# CH32V007K8U6-R0.net
KiCad netlist of a schematic drawn in Altium Designer
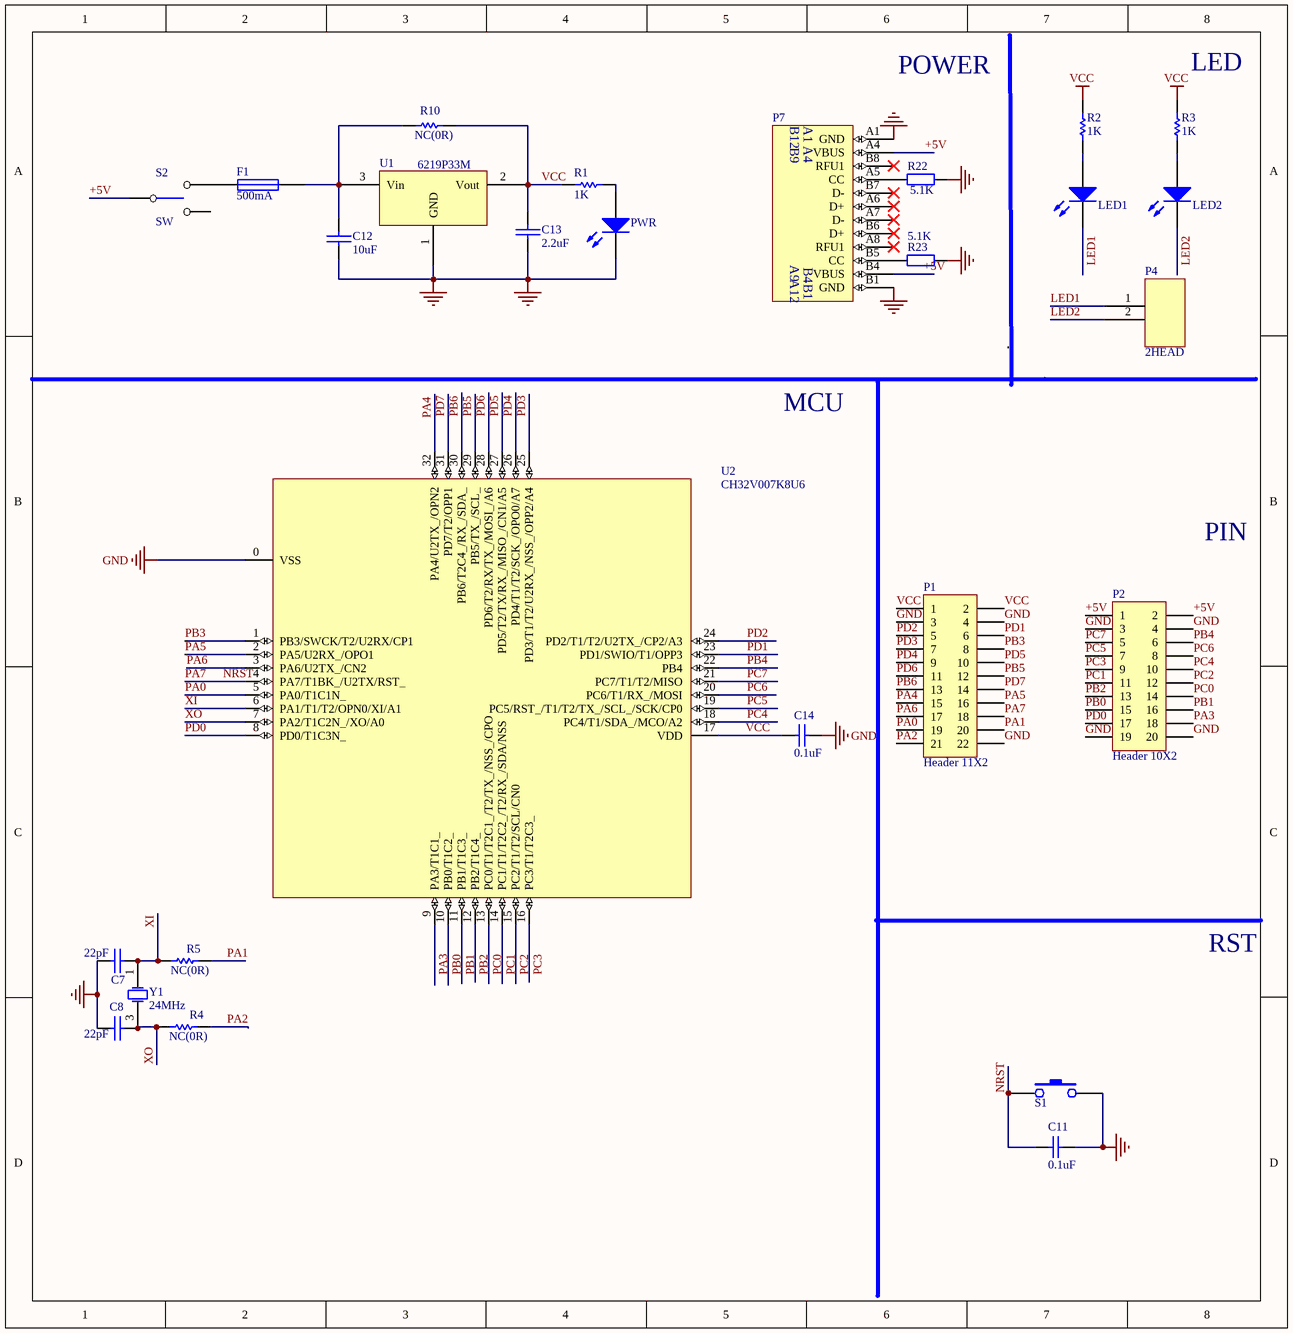
[diagram p0: CH32V007K8U6-R0.SchDoc]

(export (version "E")
  (design (tool "Eeschema 10.0.6"))
  (components
    (comp (ref "C7")
      (value "22pF")
      (footprint "0402_C")
      (description "Capacitor")
      (libsource (lib "*") (part "CAP"))
    )
    (comp (ref "C8")
      (value "22pF")
      (footprint "0402_C")
      (description "Capacitor")
      (libsource (lib "*") (part "CAP"))
    )
    (comp (ref "C11")
      (value "0.1uF")
      (footprint "0402_C")
      (description "Capacitor")
      (fields (field (name "PUBLISHER") "Altium Limited"))
      (libsource (lib "*") (part "Cap"))
    )
    (comp (ref "C12")
      (value "10uF")
      (footprint "0603_C")
      (description "Capacitor")
      (libsource (lib "wch_sch_others") (part "CAP"))
    )
    (comp (ref "C13")
      (value "2.2uF")
      (footprint "0402_C")
      (description "Capacitor")
      (libsource (lib "wch_sch_others") (part "CAP"))
    )
    (comp (ref "C14")
      (value "0.1uF")
      (footprint "0402_C")
      (description "Capacitor")
      (fields (field (name "PUBLISHER") "Altium Limited"))
      (libsource (lib "*") (part "Cap"))
    )
    (comp (ref "F1")
      (value "500mA")
      (footprint "0603")
      (description "Fuse")
      (libsource (lib "*") (part "FUSE1"))
    )
    (comp (ref "LED1")
      (value "LED1   blue")
      (footprint "0603+")
      (description "Typical INFRARED GaAs LED")
      (fields (field (name "PUBLISHER") "Altium Limited"))
      (libsource (lib "*") (part "LED0"))
    )
    (comp (ref "LED2")
      (value "LED2  blue")
      (footprint "0603+")
      (description "Typical INFRARED GaAs LED")
      (fields (field (name "PUBLISHER") "Altium Limited"))
      (libsource (lib "*") (part "LED0"))
    )
    (comp (ref "P1")
      (value "Header 11X2")
      (footprint "IDC22-2.54mm")
      (description "Header, 11-Pin, Dual row")
      (fields (field (name "PUBLISHER") "Altium Limited"))
      (libsource (lib "Miscellaneous Connectors") (part "Header 11X2"))
    )
    (comp (ref "P2")
      (value "Header 10X2")
      (footprint "IDC20-2.54mm")
      (description "Header, 10-Pin, Dual row")
      (fields (field (name "PUBLISHER") "Altium Limited"))
      (libsource (lib "Miscellaneous Connectors") (part "Header 10X2"))
    )
    (comp (ref "P4") (value "2HEAD") (footprint "SIP2-2.54mm") (libsource (lib "*") (part "2HEAD")))
    (comp (ref "P7")
      (value "TYPE-C")
      (footprint "TYPE-C-Receptacle-2.0")
      (libsource (lib "*") (part "TYPE-C1"))
    )
    (comp (ref "PWR")
      (value "POWER  red")
      (footprint "0603+")
      (description "Typical INFRARED GaAs LED")
      (fields (field (name "PUBLISHER") "Altium Limited"))
      (libsource (lib "") (part "LED0_1"))
    )
    (comp (ref "R1")
      (value "1K")
      (footprint "0402")
      (description "Semiconductor Resistor")
      (fields (field (name "PUBLISHER") "Altium Limited"))
      (libsource (lib "*") (part "Res Semi"))
    )
    (comp (ref "R2")
      (value "1K")
      (footprint "0402")
      (description "Semiconductor Resistor")
      (fields (field (name "PUBLISHER") "Altium Limited"))
      (libsource (lib "*") (part "Res Semi"))
    )
    (comp (ref "R3")
      (value "1K")
      (footprint "0402")
      (description "Semiconductor Resistor")
      (fields (field (name "PUBLISHER") "Altium Limited"))
      (libsource (lib "*") (part "Res Semi"))
    )
    (comp (ref "R4")
      (value "NC(0R)")
      (footprint "0402")
      (description "Semiconductor Resistor")
      (fields (field (name "Comment") "0R") (field (name "PUBLISHER") "Altium Limited"))
      (libsource (lib "*") (part "Res Semi"))
    )
    (comp (ref "R5")
      (value "NC(0R)")
      (footprint "0402")
      (description "Semiconductor Resistor")
      (fields (field (name "Comment") "0R") (field (name "PUBLISHER") "Altium Limited"))
      (libsource (lib "*") (part "Res Semi"))
    )
    (comp (ref "R10")
      (value "NC(0R)")
      (footprint "0402")
      (description "Semiconductor Resistor")
      (fields (field (name "Comment") "0R") (field (name "PUBLISHER") "Altium Limited"))
      (libsource (lib "*") (part "Res Semi"))
    )
    (comp (ref "R22")
      (value "5.1K")
      (footprint "0402")
      (description "Resistor")
      (libsource (lib "Miscellaneous Devices") (part "Res2"))
    )
    (comp (ref "R23")
      (value "5.1K")
      (footprint "0402")
      (description "Resistor")
      (libsource (lib "Miscellaneous Devices") (part "Res2"))
    )
    (comp (ref "S1") (value "NRST") (footprint "SMD_6.1x3.65x2.5mm-KEY") (libsource (lib "*") (part "KEY")))
    (comp (ref "S2") (value "SW") (footprint "SW1") (libsource (lib "*") (part "SW")))
    (comp (ref "U1")
      (value "6219P33M")
      (footprint "SOT-23")
      (libsource (lib "wch_sch_others") (part "6219P33M"))
    )
    (comp (ref "U2")
      (value "CH32V007K8U6")
      (footprint "QFN32_4X4")
      (description "RISC-V MCU, ADC/OPA/CMP/2*UART/I2C/SPI")
      (libsource (lib "DHXXXSCH") (part "CH32V007K8U6"))
    )
    (comp (ref "Y1")
      (value "24MHz")
      (footprint "XT3225")
      (description "Crystal Oscillator")
      (fields (field (name "PUBLISHER") "Altium Limited"))
      (libsource (lib "*") (part "XTAL"))
    )
  )
  (nets
    (net (code "1") (name "/+5V") (class "Default")
      (node (ref "P2") (pin "1") (pinfunction "1_1") (pintype "passive"))
      (node (ref "P2") (pin "2") (pinfunction "2_2") (pintype "passive"))
      (node (ref "P7") (pin "A4") (pinfunction "VBUS_A4") (pintype "bidirectional"))
      (node (ref "P7") (pin "B4") (pinfunction "VBUS_B4") (pintype "bidirectional"))
      (node (ref "S2") (pin "1") (pinfunction "1_1") (pintype "passive"))
    )
    (net (code "2") (name "/LED1") (class "Default")
      (node (ref "LED1") (pin "2") (pinfunction "K_2") (pintype "passive"))
      (node (ref "P4") (pin "1") (pintype "passive"))
    )
    (net (code "3") (name "/LED2") (class "Default")
      (node (ref "LED2") (pin "2") (pinfunction "K_2") (pintype "passive"))
      (node (ref "P4") (pin "2") (pintype "passive"))
    )
    (net (code "4") (name "/NRST") (class "Default")
      (node (ref "C11") (pin "2") (pinfunction "2_2") (pintype "passive"))
      (node (ref "P1") (pin "18") (pinfunction "18_18") (pintype "passive"))
      (node (ref "S1") (pin "1") (pinfunction "1_1") (pintype "passive"))
      (node (ref "U2") (pin "4") (pinfunction "PA7/T1BK_/U2TX/RST__4") (pintype "bidirectional"))
    )
    (net (code "5") (name "/PA0") (class "Default")
      (node (ref "P1") (pin "19") (pinfunction "19_19") (pintype "passive"))
      (node (ref "U2") (pin "5") (pinfunction "PA0/T1C1N__5") (pintype "bidirectional"))
    )
    (net (code "6") (name "/PA1") (class "Default")
      (node (ref "P1") (pin "20") (pinfunction "20_20") (pintype "passive"))
      (node (ref "R5") (pin "2") (pinfunction "2_2") (pintype "passive"))
    )
    (net (code "7") (name "/PA2") (class "Default")
      (node (ref "P1") (pin "21") (pinfunction "21_21") (pintype "passive"))
      (node (ref "R4") (pin "2") (pinfunction "2_2") (pintype "passive"))
    )
    (net (code "8") (name "/PA3") (class "Default")
      (node (ref "P2") (pin "18") (pinfunction "18_18") (pintype "passive"))
      (node (ref "U2") (pin "9") (pinfunction "PA3/T1C1__9") (pintype "bidirectional"))
    )
    (net (code "9") (name "/PA4") (class "Default")
      (node (ref "P1") (pin "15") (pinfunction "15_15") (pintype "passive"))
      (node (ref "U2") (pin "32") (pinfunction "PA4/U2TX_/OPN2_32") (pintype "bidirectional"))
    )
    (net (code "10") (name "/PA5") (class "Default")
      (node (ref "P1") (pin "16") (pinfunction "16_16") (pintype "passive"))
      (node (ref "U2") (pin "2") (pinfunction "PA5/U2RX_/OPO1_2") (pintype "bidirectional"))
    )
    (net (code "11") (name "/PA6") (class "Default")
      (node (ref "P1") (pin "17") (pinfunction "17_17") (pintype "passive"))
      (node (ref "U2") (pin "3") (pinfunction "PA6/U2TX_/CN2_3") (pintype "bidirectional"))
    )
    (net (code "12") (name "/PB0") (class "Default")
      (node (ref "P2") (pin "15") (pinfunction "15_15") (pintype "passive"))
      (node (ref "U2") (pin "10") (pinfunction "PB0/T1C2__10") (pintype "bidirectional"))
    )
    (net (code "13") (name "/PB1") (class "Default")
      (node (ref "P2") (pin "16") (pinfunction "16_16") (pintype "passive"))
      (node (ref "U2") (pin "11") (pinfunction "PB1/T1C3__11") (pintype "bidirectional"))
    )
    (net (code "14") (name "/PB2") (class "Default")
      (node (ref "P2") (pin "13") (pinfunction "13_13") (pintype "passive"))
      (node (ref "U2") (pin "12") (pinfunction "PB2/T1C4__12") (pintype "bidirectional"))
    )
    (net (code "15") (name "/PB3") (class "Default")
      (node (ref "P1") (pin "8") (pinfunction "8_8") (pintype "passive"))
      (node (ref "U2") (pin "1") (pinfunction "PB3/SWCK/T2/U2RX/CP1_1") (pintype "bidirectional"))
    )
    (net (code "16") (name "/PB4") (class "Default")
      (node (ref "P2") (pin "6") (pinfunction "6_6") (pintype "passive"))
      (node (ref "U2") (pin "22") (pinfunction "PB4_22") (pintype "bidirectional"))
    )
    (net (code "17") (name "/PB5") (class "Default")
      (node (ref "P1") (pin "12") (pinfunction "12_12") (pintype "passive"))
      (node (ref "U2") (pin "29") (pinfunction "PB5/TX_/SCL__29") (pintype "bidirectional"))
    )
    (net (code "18") (name "/PB6") (class "Default")
      (node (ref "P1") (pin "13") (pinfunction "13_13") (pintype "passive"))
      (node (ref "U2") (pin "30") (pinfunction "PB6/T2C4_/RX_/SDA__30") (pintype "bidirectional"))
    )
    (net (code "19") (name "/PC0") (class "Default")
      (node (ref "P2") (pin "14") (pinfunction "14_14") (pintype "passive"))
      (node (ref "U2") (pin "13") (pinfunction "PC0/T1/T2C1_/T2/TX_/NSS_/CPO_13") (pintype "bidirectional"))
    )
    (net (code "20") (name "/PC1") (class "Default")
      (node (ref "P2") (pin "11") (pinfunction "11_11") (pintype "passive"))
      (node (ref "U2") (pin "14") (pinfunction "PC1/T1/T2C2_/T2/RX_/SDA/NSS_14") (pintype "bidirectional"))
    )
    (net (code "21") (name "/PC2") (class "Default")
      (node (ref "P2") (pin "12") (pinfunction "12_12") (pintype "passive"))
      (node (ref "U2") (pin "15") (pinfunction "PC2/T1/T2/SCL/CN0_15") (pintype "bidirectional"))
    )
    (net (code "22") (name "/PC3") (class "Default")
      (node (ref "P2") (pin "9") (pinfunction "9_9") (pintype "passive"))
      (node (ref "U2") (pin "16") (pinfunction "PC3/T1/T2C3__16") (pintype "bidirectional"))
    )
    (net (code "23") (name "/PC4") (class "Default")
      (node (ref "P2") (pin "10") (pinfunction "10_10") (pintype "passive"))
      (node (ref "U2") (pin "18") (pinfunction "PC4/T1/SDA_/MCO/A2_18") (pintype "bidirectional"))
    )
    (net (code "24") (name "/PC5") (class "Default")
      (node (ref "P2") (pin "7") (pinfunction "7_7") (pintype "passive"))
      (node (ref "U2") (pin "19") (pinfunction "PC5/RST_/T1/T2/TX_/SCL_/SCK/CP0_19") (pintype "bidirectional"))
    )
    (net (code "25") (name "/PC6") (class "Default")
      (node (ref "P2") (pin "8") (pinfunction "8_8") (pintype "passive"))
      (node (ref "U2") (pin "20") (pinfunction "PC6/T1/RX_/MOSI_20") (pintype "bidirectional"))
    )
    (net (code "26") (name "/PC7") (class "Default")
      (node (ref "P2") (pin "5") (pinfunction "5_5") (pintype "passive"))
      (node (ref "U2") (pin "21") (pinfunction "PC7/T1/T2/MISO_21") (pintype "bidirectional"))
    )
    (net (code "27") (name "/PD0") (class "Default")
      (node (ref "P2") (pin "17") (pinfunction "17_17") (pintype "passive"))
      (node (ref "U2") (pin "8") (pinfunction "PD0/T1C3N__8") (pintype "bidirectional"))
    )
    (net (code "28") (name "/PD1") (class "Default")
      (node (ref "P1") (pin "6") (pinfunction "6_6") (pintype "passive"))
      (node (ref "U2") (pin "23") (pinfunction "PD1/SWIO/T1/OPP3_23") (pintype "bidirectional"))
    )
    (net (code "29") (name "/PD2") (class "Default")
      (node (ref "P1") (pin "5") (pinfunction "5_5") (pintype "passive"))
      (node (ref "U2") (pin "24") (pinfunction "PD2/T1/T2/U2TX_/CP2/A3_24") (pintype "bidirectional"))
    )
    (net (code "30") (name "/PD3") (class "Default")
      (node (ref "P1") (pin "7") (pinfunction "7_7") (pintype "passive"))
      (node (ref "U2") (pin "25") (pinfunction "PD3/T1/T2/U2RX_/NSS_/OPP2/A4_25") (pintype "bidirectional"))
    )
    (net (code "31") (name "/PD4") (class "Default")
      (node (ref "P1") (pin "9") (pinfunction "9_9") (pintype "passive"))
      (node (ref "U2") (pin "26") (pinfunction "PD4/T1/T2/SCK_/OPO0/A7_26") (pintype "bidirectional"))
    )
    (net (code "32") (name "/PD5") (class "Default")
      (node (ref "P1") (pin "10") (pinfunction "10_10") (pintype "passive"))
      (node (ref "U2") (pin "27") (pinfunction "PD5/T2/TX/RX_/MISO_/CN1/A5_27") (pintype "bidirectional"))
    )
    (net (code "33") (name "/PD6") (class "Default")
      (node (ref "P1") (pin "11") (pinfunction "11_11") (pintype "passive"))
      (node (ref "U2") (pin "28") (pinfunction "PD6/T2/RX/TX_/MOSI_/A6_28") (pintype "bidirectional"))
    )
    (net (code "34") (name "/PD7") (class "Default")
      (node (ref "P1") (pin "14") (pinfunction "14_14") (pintype "passive"))
      (node (ref "U2") (pin "31") (pinfunction "PD7/T2/OPP1_31") (pintype "bidirectional"))
    )
    (net (code "35") (name "/XI") (class "Default")
      (node (ref "C7") (pin "2") (pinfunction "2_2") (pintype "passive"))
      (node (ref "R5") (pin "1") (pinfunction "1_1") (pintype "passive"))
      (node (ref "U2") (pin "6") (pinfunction "PA1/T1/T2/OPN0/XI/A1_6") (pintype "bidirectional"))
      (node (ref "Y1") (pin "1") (pinfunction "OSC1_1") (pintype "passive"))
    )
    (net (code "36") (name "/XO") (class "Default")
      (node (ref "C8") (pin "2") (pinfunction "2_2") (pintype "passive"))
      (node (ref "R4") (pin "1") (pinfunction "1_1") (pintype "passive"))
      (node (ref "U2") (pin "7") (pinfunction "PA2/T1C2N_/XO/A0_7") (pintype "bidirectional"))
      (node (ref "Y1") (pin "3") (pinfunction "OSC2_3") (pintype "passive"))
    )
    (net (code "37") (name "GND") (class "Default")
      (node (ref "C11") (pin "1") (pinfunction "1_1") (pintype "passive"))
      (node (ref "C12") (pin "2") (pinfunction "2_2") (pintype "passive"))
      (node (ref "C13") (pin "1") (pinfunction "1_1") (pintype "passive"))
      (node (ref "C14") (pin "2") (pinfunction "2_2") (pintype "passive"))
      (node (ref "C7") (pin "1") (pinfunction "1_1") (pintype "passive"))
      (node (ref "C8") (pin "1") (pinfunction "1_1") (pintype "passive"))
      (node (ref "P1") (pin "22") (pinfunction "22_22") (pintype "passive"))
      (node (ref "P1") (pin "3") (pinfunction "3_3") (pintype "passive"))
      (node (ref "P1") (pin "4") (pinfunction "4_4") (pintype "passive"))
      (node (ref "P2") (pin "19") (pinfunction "19_19") (pintype "passive"))
      (node (ref "P2") (pin "20") (pinfunction "20_20") (pintype "passive"))
      (node (ref "P2") (pin "3") (pinfunction "3_3") (pintype "passive"))
      (node (ref "P2") (pin "4") (pinfunction "4_4") (pintype "passive"))
      (node (ref "P7") (pin "A1") (pinfunction "GND_A1") (pintype "bidirectional"))
      (node (ref "P7") (pin "B1") (pinfunction "GND_B1") (pintype "bidirectional"))
      (node (ref "PWR") (pin "2") (pinfunction "K_2") (pintype "passive"))
      (node (ref "R22") (pin "2") (pinfunction "2_2") (pintype "passive"))
      (node (ref "R23") (pin "2") (pinfunction "2_2") (pintype "passive"))
      (node (ref "S1") (pin "2") (pinfunction "2_2") (pintype "passive"))
      (node (ref "U1") (pin "1") (pinfunction "GND_1") (pintype "passive"))
      (node (ref "U2") (pin "0") (pinfunction "VSS_0") (pintype "power_in"))
    )
    (net (code "38") (name "Net-(F1-Pad1)") (class "Default")
      (node (ref "F1") (pin "1") (pinfunction "1_1") (pintype "passive"))
      (node (ref "S2") (pin "3") (pinfunction "3_3") (pintype "passive"))
    )
    (net (code "39") (name "Net-(LED1-A)") (class "Default")
      (node (ref "LED1") (pin "1") (pinfunction "A_1") (pintype "passive"))
      (node (ref "R2") (pin "2") (pinfunction "2_2") (pintype "passive"))
    )
    (net (code "40") (name "Net-(LED2-A)") (class "Default")
      (node (ref "LED2") (pin "1") (pinfunction "A_1") (pintype "passive"))
      (node (ref "R3") (pin "2") (pinfunction "2_2") (pintype "passive"))
    )
    (net (code "41") (name "Net-(P7-CC-PadA5)") (class "Default")
      (node (ref "P7") (pin "A5") (pinfunction "CC_A5") (pintype "bidirectional"))
      (node (ref "R22") (pin "1") (pinfunction "1_1") (pintype "passive"))
    )
    (net (code "42") (name "Net-(P7-CC-PadB5)") (class "Default")
      (node (ref "P7") (pin "B5") (pinfunction "CC_B5") (pintype "bidirectional"))
      (node (ref "R23") (pin "1") (pinfunction "1_1") (pintype "passive"))
    )
    (net (code "43") (name "Net-(PWR-A)") (class "Default")
      (node (ref "PWR") (pin "1") (pinfunction "A_1") (pintype "passive"))
      (node (ref "R1") (pin "1") (pinfunction "1_1") (pintype "passive"))
    )
    (net (code "44") (name "Net-(U1-Vin)") (class "Default")
      (node (ref "C12") (pin "1") (pinfunction "1_1") (pintype "passive"))
      (node (ref "F1") (pin "2") (pinfunction "2_2") (pintype "passive"))
      (node (ref "R10") (pin "1") (pinfunction "1_1") (pintype "passive"))
      (node (ref "U1") (pin "3") (pinfunction "Vin_3") (pintype "passive"))
    )
    (net (code "45") (name "VCC") (class "Default")
      (node (ref "C13") (pin "2") (pinfunction "2_2") (pintype "passive"))
      (node (ref "C14") (pin "1") (pinfunction "1_1") (pintype "passive"))
      (node (ref "P1") (pin "1") (pinfunction "1_1") (pintype "passive"))
      (node (ref "P1") (pin "2") (pinfunction "2_2") (pintype "passive"))
      (node (ref "R1") (pin "2") (pinfunction "2_2") (pintype "passive"))
      (node (ref "R10") (pin "2") (pinfunction "2_2") (pintype "passive"))
      (node (ref "R2") (pin "1") (pinfunction "1_1") (pintype "passive"))
      (node (ref "R3") (pin "1") (pinfunction "1_1") (pintype "passive"))
      (node (ref "U1") (pin "2") (pinfunction "Vout_2") (pintype "passive"))
      (node (ref "U2") (pin "17") (pinfunction "VDD_17") (pintype "power_in"))
    )
    (net (code "46") (name "unconnected-(P7-D+-PadA6)") (class "Default")
      (node (ref "P7") (pin "A6") (pinfunction "D+_A6") (pintype "bidirectional+no_connect"))
    )
    (net (code "47") (name "unconnected-(P7-D+-PadB6)") (class "Default")
      (node (ref "P7") (pin "B6") (pinfunction "D+_B6") (pintype "bidirectional+no_connect"))
    )
    (net (code "48") (name "unconnected-(P7-D--PadA7)") (class "Default")
      (node (ref "P7") (pin "A7") (pinfunction "D-_A7") (pintype "bidirectional+no_connect"))
    )
    (net (code "49") (name "unconnected-(P7-D--PadB7)") (class "Default")
      (node (ref "P7") (pin "B7") (pinfunction "D-_B7") (pintype "bidirectional+no_connect"))
    )
    (net (code "50") (name "unconnected-(P7-RFU1-PadA8)") (class "Default")
      (node (ref "P7") (pin "A8") (pinfunction "RFU1_A8") (pintype "bidirectional+no_connect"))
    )
    (net (code "51") (name "unconnected-(P7-RFU1-PadB8)") (class "Default")
      (node (ref "P7") (pin "B8") (pinfunction "RFU1_B8") (pintype "bidirectional+no_connect"))
    )
    (net (code "52") (name "unconnected-(S2-Pad2)") (class "Default")
      (node (ref "S2") (pin "2") (pinfunction "2_2") (pintype "passive"))
    )
  )
)
